# MC3_module.net
KiCad netlist of a schematic drawn in Altium Designer
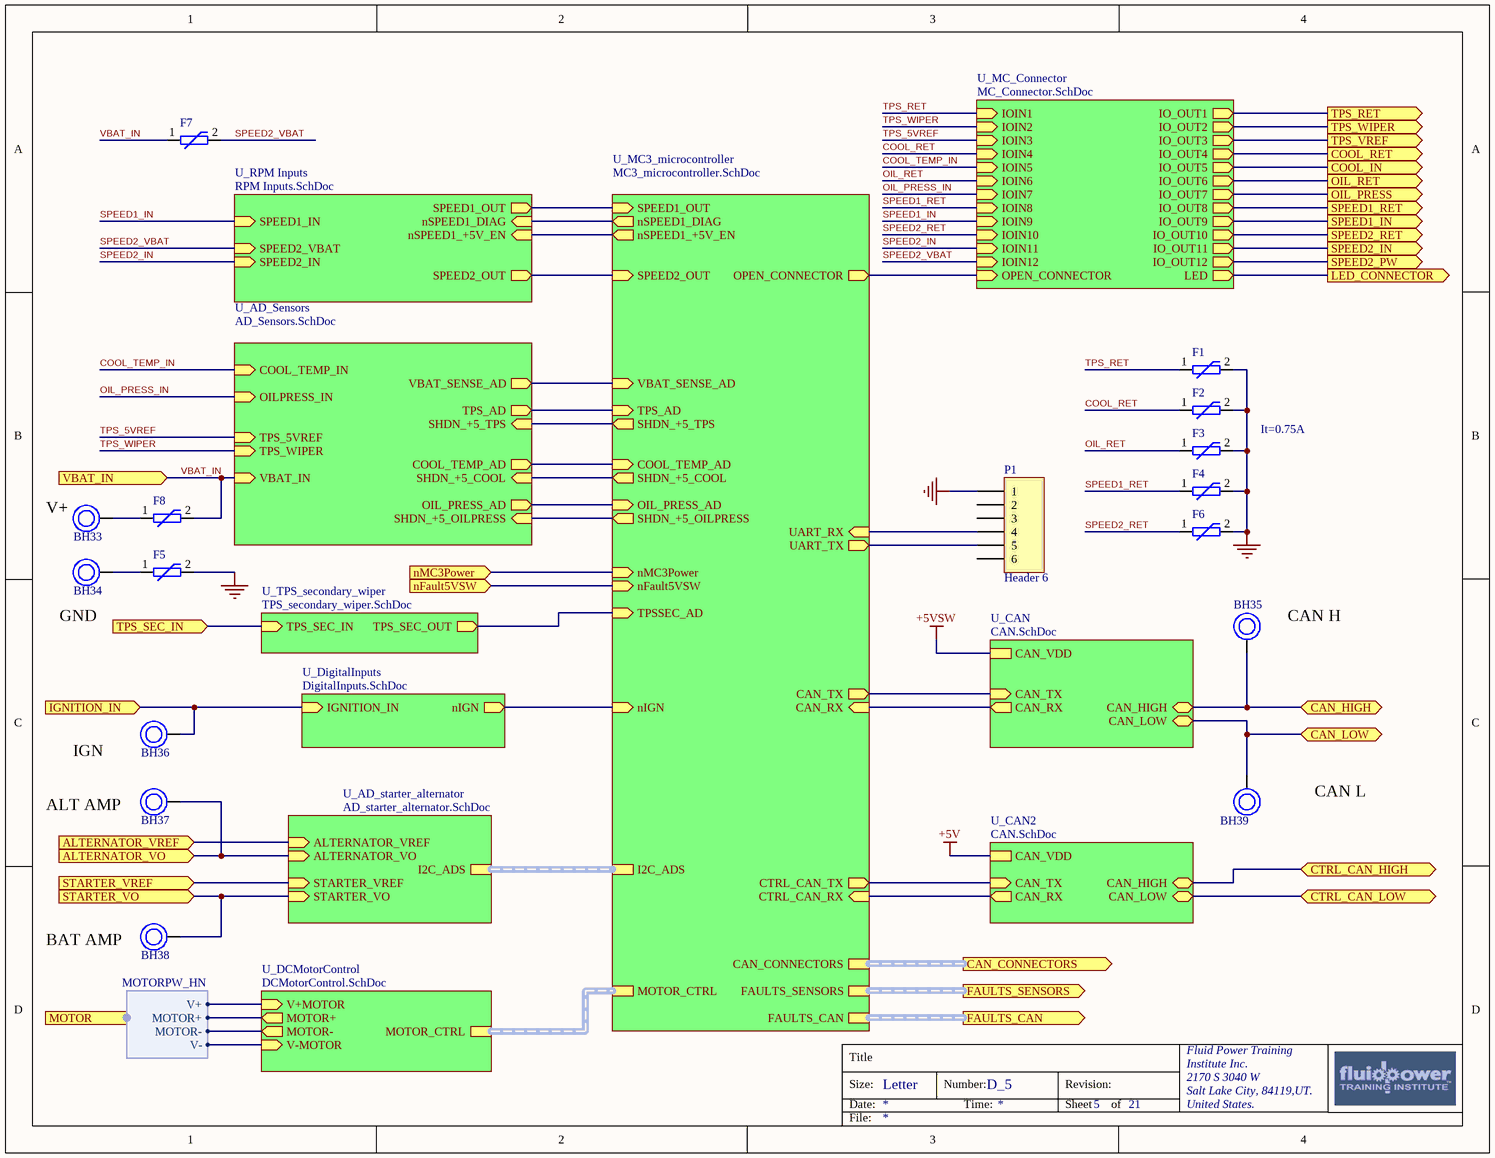
[diagram p0: MC3_module.SchDoc]

(export (version "E")
  (design (tool "Eeschema 10.0.6"))
  (components
    (comp (ref "BH33")
      (value "BananaHole")
      (footprint "MC1:BananaHole")
      (description "Banana hole for panel testing and board mounting")
      (libsource (lib "MC1") (part "BananaHole"))
    )
    (comp (ref "BH34")
      (value "BananaHole")
      (footprint "MC1:BananaHole")
      (description "Banana hole for panel testing and board mounting")
      (libsource (lib "MC1") (part "BananaHole"))
    )
    (comp (ref "BH35")
      (value "BananaHole")
      (footprint "MC1:BananaHole")
      (description "Banana hole for panel testing and board mounting")
      (libsource (lib "MC1") (part "BananaHole"))
    )
    (comp (ref "BH36")
      (value "BananaHole")
      (footprint "MC1:BananaHole")
      (description "Banana hole for panel testing and board mounting")
      (libsource (lib "MC1") (part "BananaHole"))
    )
    (comp (ref "BH37")
      (value "BananaHole")
      (footprint "MC1:BananaHole")
      (description "Banana hole for panel testing and board mounting")
      (libsource (lib "MC1") (part "BananaHole"))
    )
    (comp (ref "BH38")
      (value "BananaHole")
      (footprint "MC1:BananaHole")
      (description "Banana hole for panel testing and board mounting")
      (libsource (lib "MC1") (part "BananaHole"))
    )
    (comp (ref "BH39")
      (value "BananaHole")
      (footprint "MC1:BananaHole")
      (description "Banana hole for panel testing and board mounting")
      (libsource (lib "MC1") (part "BananaHole"))
    )
    (comp (ref "F1")
      (value "It=0.75A")
      (footprint "MC1:0ZCJ0035AF2E_FUSE")
      (description "PTC RESET FUSE 30V 350MA 1206")
      (fields (field (name "MANUFACTURER") "Bel") (field (name "MANUFACTURER PART NUMBER") "0ZCJ0035AF2E"))
      (libsource (lib "MC1") (part "0ZCJ0035AF2E"))
    )
    (comp (ref "F2")
      (value "It=0.75A")
      (footprint "MC1:0ZCJ0035AF2E_FUSE")
      (description "PTC RESET FUSE 30V 350MA 1206")
      (fields (field (name "MANUFACTURER") "Bel") (field (name "MANUFACTURER PART NUMBER") "0ZCJ0035AF2E"))
      (libsource (lib "MC1") (part "0ZCJ0035AF2E"))
    )
    (comp (ref "F3")
      (value "It=0.75A")
      (footprint "MC1:0ZCJ0035AF2E_FUSE")
      (description "PTC RESET FUSE 30V 350MA 1206")
      (fields (field (name "MANUFACTURER") "Bel") (field (name "MANUFACTURER PART NUMBER") "0ZCJ0035AF2E"))
      (libsource (lib "MC1") (part "0ZCJ0035AF2E"))
    )
    (comp (ref "F4")
      (value "It=0.75A")
      (footprint "MC1:0ZCJ0035AF2E_FUSE")
      (description "PTC RESET FUSE 30V 350MA 1206")
      (fields (field (name "MANUFACTURER") "Bel") (field (name "MANUFACTURER PART NUMBER") "0ZCJ0035AF2E"))
      (libsource (lib "MC1") (part "0ZCJ0035AF2E"))
    )
    (comp (ref "F5")
      (value "It=0.75A")
      (footprint "MC1:0ZCJ0035AF2E_FUSE")
      (description "PTC RESET FUSE 30V 350MA 1206")
      (fields (field (name "MANUFACTURER") "Bel") (field (name "MANUFACTURER PART NUMBER") "0ZCJ0035AF2E"))
      (libsource (lib "MC1") (part "0ZCJ0035AF2E"))
    )
    (comp (ref "F6")
      (value "It=0.75A")
      (footprint "MC1:0ZCJ0035AF2E_FUSE")
      (description "PTC RESET FUSE 30V 350MA 1206")
      (fields (field (name "MANUFACTURER") "Bel") (field (name "MANUFACTURER PART NUMBER") "0ZCJ0035AF2E"))
      (libsource (lib "MC1") (part "0ZCJ0035AF2E"))
    )
    (comp (ref "F7")
      (value "It=0.75A")
      (footprint "MC1:0ZCJ0035AF2E_FUSE")
      (description "PTC RESET FUSE 30V 350MA 1206")
      (fields (field (name "MANUFACTURER") "Bel") (field (name "MANUFACTURER PART NUMBER") "0ZCJ0035AF2E"))
      (libsource (lib "MC1") (part "0ZCJ0035AF2E"))
    )
    (comp (ref "F8")
      (value "It=0.75A")
      (footprint "MC1:0ZCJ0035AF2E_FUSE")
      (description "PTC RESET FUSE 30V 350MA 1206")
      (fields (field (name "MANUFACTURER") "Bel") (field (name "MANUFACTURER PART NUMBER") "0ZCJ0035AF2E"))
      (libsource (lib "MC1") (part "0ZCJ0035AF2E"))
    )
    (comp (ref "P1")
      (value "Header 6")
      (footprint "HDR1X6")
      (description "Header, 6-Pin")
      (fields (field (name "PUBLISHER") "Altium Limited"))
      (libsource (lib "Miscellaneous Connectors") (part "Header 6"))
    )
  )
  (nets
    (net (code "7") (name "/ALTERNATOR_VO") (class "Default")
      (node (ref "BH37") (pin "1") (pinfunction "1_1") (pintype "passive"))
    )
    (net (code "10") (name "/CAN_HIGH") (class "Default")
      (node (ref "BH35") (pin "1") (pinfunction "1_1") (pintype "passive"))
    )
    (net (code "11") (name "/CAN_LOW") (class "Default")
      (node (ref "BH39") (pin "1") (pinfunction "1_1") (pintype "passive"))
    )
    (net (code "16") (name "/COOL_RET") (class "Default")
      (node (ref "F2") (pin "1") (pinfunction "1_1") (pintype "passive"))
    )
    (net (code "25") (name "/IGNITION_IN") (class "Default")
      (node (ref "BH36") (pin "1") (pinfunction "1_1") (pintype "passive"))
    )
    (net (code "33") (name "/OIL_RET") (class "Default")
      (node (ref "F3") (pin "1") (pinfunction "1_1") (pintype "passive"))
    )
    (net (code "40") (name "/SPEED1_RET") (class "Default")
      (node (ref "F4") (pin "1") (pinfunction "1_1") (pintype "passive"))
    )
    (net (code "44") (name "/SPEED2_RET") (class "Default")
      (node (ref "F6") (pin "1") (pinfunction "1_1") (pintype "passive"))
    )
    (net (code "45") (name "/SPEED2_VBAT") (class "Default")
      (node (ref "F7") (pin "2") (pinfunction "2_2") (pintype "passive"))
    )
    (net (code "46") (name "/STARTER_VO") (class "Default")
      (node (ref "BH38") (pin "1") (pinfunction "1_1") (pintype "passive"))
    )
    (net (code "50") (name "/TPS_RET") (class "Default")
      (node (ref "F1") (pin "1") (pinfunction "1_1") (pintype "passive"))
    )
    (net (code "55") (name "/UART_RX") (class "Default")
      (node (ref "P1") (pin "4") (pinfunction "4_4") (pintype "passive"))
    )
    (net (code "56") (name "/UART_TX") (class "Default")
      (node (ref "P1") (pin "5") (pinfunction "5_5") (pintype "passive"))
    )
    (net (code "59") (name "/VBAT_IN") (class "Default")
      (node (ref "F7") (pin "1") (pinfunction "1_1") (pintype "passive"))
      (node (ref "F8") (pin "2") (pinfunction "2_2") (pintype "passive"))
    )
    (net (code "67") (name "GND") (class "Default")
      (node (ref "F1") (pin "2") (pinfunction "2_2") (pintype "passive"))
      (node (ref "F2") (pin "2") (pinfunction "2_2") (pintype "passive"))
      (node (ref "F3") (pin "2") (pinfunction "2_2") (pintype "passive"))
      (node (ref "F4") (pin "2") (pinfunction "2_2") (pintype "passive"))
      (node (ref "F5") (pin "2") (pinfunction "2_2") (pintype "passive"))
      (node (ref "F6") (pin "2") (pinfunction "2_2") (pintype "passive"))
      (node (ref "P1") (pin "1") (pinfunction "1_1") (pintype "passive"))
    )
    (net (code "68") (name "Net-(BH33-Pad1)") (class "Default")
      (node (ref "BH33") (pin "1") (pinfunction "1_1") (pintype "passive"))
      (node (ref "F8") (pin "1") (pinfunction "1_1") (pintype "passive"))
    )
    (net (code "69") (name "Net-(BH34-Pad1)") (class "Default")
      (node (ref "BH34") (pin "1") (pinfunction "1_1") (pintype "passive"))
      (node (ref "F5") (pin "1") (pinfunction "1_1") (pintype "passive"))
    )
    (net (code "70") (name "unconnected-(P1-Pad2)") (class "Default")
      (node (ref "P1") (pin "2") (pinfunction "2_2") (pintype "passive"))
    )
    (net (code "71") (name "unconnected-(P1-Pad3)") (class "Default")
      (node (ref "P1") (pin "3") (pinfunction "3_3") (pintype "passive"))
    )
    (net (code "72") (name "unconnected-(P1-Pad6)") (class "Default")
      (node (ref "P1") (pin "6") (pinfunction "6_6") (pintype "passive"))
    )
  )
)
